# Relays.net
KiCad netlist of a schematic drawn in Altium Designer
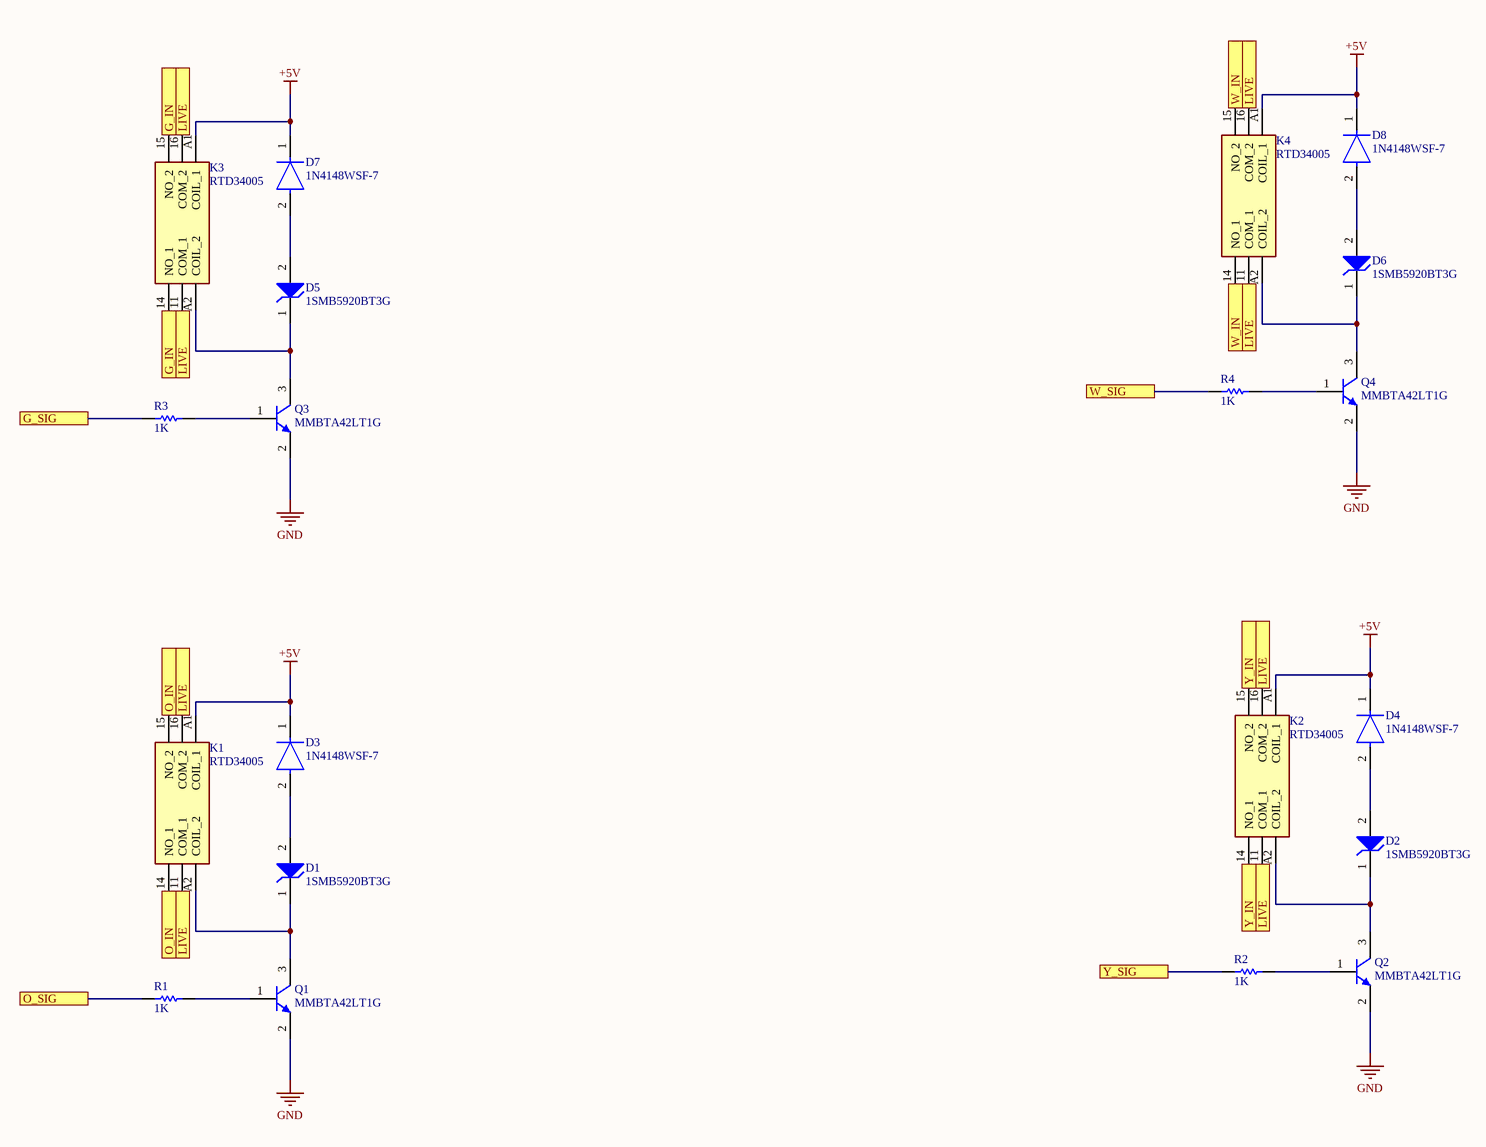
[diagram p0: Relays.SchDoc]

(export (version "E")
  (design (tool "Eeschema 10.0.6"))
  (components
    (comp (ref "D1")
      (value "1SMB5920BT3G")
      (footprint "ONSC-SMB-2-403A-03_H_V")
      (description "3 W Zener Voltage Regulator, 2-Pin SMB, Pb-Free, Tape and Reel")
      (fields (field (name "MANUFACTURER") "On Semiconductor"))
      (libsource (lib "Altium Content Vault") (part "ONSC-K1A2-2"))
    )
    (comp (ref "D2")
      (value "1SMB5920BT3G")
      (footprint "ONSC-SMB-2-403A-03_H_V")
      (description "3 W Zener Voltage Regulator, 2-Pin SMB, Pb-Free, Tape and Reel")
      (fields (field (name "MANUFACTURER") "On Semiconductor"))
      (libsource (lib "Altium Content Vault") (part "ONSC-K1A2-2"))
    )
    (comp (ref "D3")
      (value "1N4148WSF-7")
      (footprint "FP-SOD323F-MFG")
      (description "DIODE GEN PURP 100V 250MA SOD323")
      (fields
        (field (name "MANUFACTURER") "Diodes Inc.")
        (field (name "OCTOPART") "https://octopart.com/1n4148wsf-7-diodes+inc.-33798544")
      )
      (libsource (lib "Altium Content Vault") (part "d7152d700b627762746794eb795d46e"))
    )
    (comp (ref "D4")
      (value "1N4148WSF-7")
      (footprint "FP-SOD323F-MFG")
      (description "DIODE GEN PURP 100V 250MA SOD323")
      (fields
        (field (name "MANUFACTURER") "Diodes Inc.")
        (field (name "OCTOPART") "https://octopart.com/1n4148wsf-7-diodes+inc.-33798544")
      )
      (libsource (lib "Altium Content Vault") (part "d7152d700b627762746794eb795d46e"))
    )
    (comp (ref "D5")
      (value "1SMB5920BT3G")
      (footprint "ONSC-SMB-2-403A-03_H_V")
      (description "3 W Zener Voltage Regulator, 2-Pin SMB, Pb-Free, Tape and Reel")
      (fields (field (name "MANUFACTURER") "On Semiconductor"))
      (libsource (lib "Altium Content Vault") (part "ONSC-K1A2-2"))
    )
    (comp (ref "D6")
      (value "1SMB5920BT3G")
      (footprint "ONSC-SMB-2-403A-03_H_V")
      (description "3 W Zener Voltage Regulator, 2-Pin SMB, Pb-Free, Tape and Reel")
      (fields (field (name "MANUFACTURER") "On Semiconductor"))
      (libsource (lib "Altium Content Vault") (part "ONSC-K1A2-2"))
    )
    (comp (ref "D7")
      (value "1N4148WSF-7")
      (footprint "FP-SOD323F-MFG")
      (description "DIODE GEN PURP 100V 250MA SOD323")
      (fields
        (field (name "MANUFACTURER") "Diodes Inc.")
        (field (name "OCTOPART") "https://octopart.com/1n4148wsf-7-diodes+inc.-33798544")
      )
      (libsource (lib "Altium Content Vault") (part "d7152d700b627762746794eb795d46e"))
    )
    (comp (ref "D8")
      (value "1N4148WSF-7")
      (footprint "FP-SOD323F-MFG")
      (description "DIODE GEN PURP 100V 250MA SOD323")
      (fields
        (field (name "MANUFACTURER") "Diodes Inc.")
        (field (name "OCTOPART") "https://octopart.com/1n4148wsf-7-diodes+inc.-33798544")
      )
      (libsource (lib "Altium Content Vault") (part "d7152d700b627762746794eb795d46e"))
    )
    (comp (ref "K1")
      (value "RTD34005")
      (footprint "SamacSys:RTD34005")
      (description "Relay or Contactor")
      (fields (field (name "MOUSER PART NUMBER") "655-RTD34005"))
      (libsource (lib "*") (part "RTD34005"))
    )
    (comp (ref "K2")
      (value "RTD34005")
      (footprint "SamacSys:RTD34005")
      (description "Relay or Contactor")
      (fields (field (name "MOUSER PART NUMBER") "655-RTD34005"))
      (libsource (lib "*") (part "RTD34005"))
    )
    (comp (ref "K3")
      (value "RTD34005")
      (footprint "SamacSys:RTD34005")
      (description "Relay or Contactor")
      (fields (field (name "MOUSER PART NUMBER") "655-RTD34005"))
      (libsource (lib "*") (part "RTD34005"))
    )
    (comp (ref "K4")
      (value "RTD34005")
      (footprint "SamacSys:RTD34005")
      (description "Relay or Contactor")
      (fields (field (name "MOUSER PART NUMBER") "655-RTD34005"))
      (libsource (lib "*") (part "RTD34005"))
    )
    (comp (ref "Q1")
      (value "MMBTA42LT1G")
      (footprint "ONSC-SOT-23-3-318-08_V")
      (description "High Voltage Transistor, NPN Silicon, 3-Pin SOT-23, Pb-Free, Tape and Reel")
      (fields (field (name "MANUFACTURER") "On Semiconductor"))
      (libsource (lib "Altium Content Vault") (part "ONSC-NPN-B1E2C3-3"))
    )
    (comp (ref "Q2")
      (value "MMBTA42LT1G")
      (footprint "ONSC-SOT-23-3-318-08_V")
      (description "High Voltage Transistor, NPN Silicon, 3-Pin SOT-23, Pb-Free, Tape and Reel")
      (fields (field (name "MANUFACTURER") "On Semiconductor"))
      (libsource (lib "Altium Content Vault") (part "ONSC-NPN-B1E2C3-3"))
    )
    (comp (ref "Q3")
      (value "MMBTA42LT1G")
      (footprint "ONSC-SOT-23-3-318-08_V")
      (description "High Voltage Transistor, NPN Silicon, 3-Pin SOT-23, Pb-Free, Tape and Reel")
      (fields (field (name "MANUFACTURER") "On Semiconductor"))
      (libsource (lib "Altium Content Vault") (part "ONSC-NPN-B1E2C3-3"))
    )
    (comp (ref "Q4")
      (value "MMBTA42LT1G")
      (footprint "ONSC-SOT-23-3-318-08_V")
      (description "High Voltage Transistor, NPN Silicon, 3-Pin SOT-23, Pb-Free, Tape and Reel")
      (fields (field (name "MANUFACTURER") "On Semiconductor"))
      (libsource (lib "Altium Content Vault") (part "ONSC-NPN-B1E2C3-3"))
    )
    (comp (ref "R1")
      (value "1K")
      (footprint "RESC1608X55X30LL20T20")
      (fields (field (name "MANUFACTURER") "Panasonic") (field (name "PART NUMBER") "ERA3AEB102V"))
      (libsource (lib "Altium Content Vault") (part "RES"))
    )
    (comp (ref "R2")
      (value "1K")
      (footprint "RESC1608X55X30LL20T20")
      (fields (field (name "MANUFACTURER") "Panasonic") (field (name "PART NUMBER") "ERA3AEB102V"))
      (libsource (lib "Altium Content Vault") (part "RES"))
    )
    (comp (ref "R3")
      (value "1K")
      (footprint "RESC1608X55X30LL20T20")
      (fields (field (name "MANUFACTURER") "Panasonic") (field (name "PART NUMBER") "ERA3AEB102V"))
      (libsource (lib "Altium Content Vault") (part "RES"))
    )
    (comp (ref "R4")
      (value "1K")
      (footprint "RESC1608X55X30LL20T20")
      (fields (field (name "MANUFACTURER") "Panasonic") (field (name "PART NUMBER") "ERA3AEB102V"))
      (libsource (lib "Altium Content Vault") (part "RES"))
    )
  )
  (nets
    (net (code "1") (name "+5V") (class "Default")
      (node (ref "D3") (pin "1") (pinfunction "C_1") (pintype "passive"))
      (node (ref "D4") (pin "1") (pinfunction "C_1") (pintype "passive"))
      (node (ref "D7") (pin "1") (pinfunction "C_1") (pintype "passive"))
      (node (ref "D8") (pin "1") (pinfunction "C_1") (pintype "passive"))
      (node (ref "K1") (pin "A1") (pinfunction "COIL_1_A1") (pintype "passive"))
      (node (ref "K2") (pin "A1") (pinfunction "COIL_1_A1") (pintype "passive"))
      (node (ref "K3") (pin "A1") (pinfunction "COIL_1_A1") (pintype "passive"))
      (node (ref "K4") (pin "A1") (pinfunction "COIL_1_A1") (pintype "passive"))
    )
    (net (code "2") (name "/G_IN") (class "Default")
      (node (ref "K3") (pin "14") (pinfunction "NO_1_14") (pintype "passive"))
      (node (ref "K3") (pin "15") (pinfunction "NO_2_15") (pintype "passive"))
    )
    (net (code "3") (name "/G_SIG") (class "Default")
      (node (ref "R3") (pin "1") (pinfunction "1_1") (pintype "passive"))
    )
    (net (code "4") (name "/LIVE") (class "Default")
      (node (ref "K1") (pin "11") (pinfunction "COM_1_11") (pintype "passive"))
      (node (ref "K1") (pin "16") (pinfunction "COM_2_16") (pintype "passive"))
      (node (ref "K2") (pin "11") (pinfunction "COM_1_11") (pintype "passive"))
      (node (ref "K2") (pin "16") (pinfunction "COM_2_16") (pintype "passive"))
      (node (ref "K3") (pin "11") (pinfunction "COM_1_11") (pintype "passive"))
      (node (ref "K3") (pin "16") (pinfunction "COM_2_16") (pintype "passive"))
      (node (ref "K4") (pin "11") (pinfunction "COM_1_11") (pintype "passive"))
      (node (ref "K4") (pin "16") (pinfunction "COM_2_16") (pintype "passive"))
    )
    (net (code "5") (name "/O_IN") (class "Default")
      (node (ref "K1") (pin "14") (pinfunction "NO_1_14") (pintype "passive"))
      (node (ref "K1") (pin "15") (pinfunction "NO_2_15") (pintype "passive"))
    )
    (net (code "6") (name "/O_SIG") (class "Default")
      (node (ref "R1") (pin "1") (pinfunction "1_1") (pintype "passive"))
    )
    (net (code "7") (name "/W_IN") (class "Default")
      (node (ref "K4") (pin "14") (pinfunction "NO_1_14") (pintype "passive"))
      (node (ref "K4") (pin "15") (pinfunction "NO_2_15") (pintype "passive"))
    )
    (net (code "8") (name "/W_SIG") (class "Default")
      (node (ref "R4") (pin "1") (pinfunction "1_1") (pintype "passive"))
    )
    (net (code "9") (name "/Y_IN") (class "Default")
      (node (ref "K2") (pin "14") (pinfunction "NO_1_14") (pintype "passive"))
      (node (ref "K2") (pin "15") (pinfunction "NO_2_15") (pintype "passive"))
    )
    (net (code "10") (name "/Y_SIG") (class "Default")
      (node (ref "R2") (pin "1") (pinfunction "1_1") (pintype "passive"))
    )
    (net (code "11") (name "GND") (class "Default")
      (node (ref "Q1") (pin "2") (pinfunction "E_2") (pintype "passive"))
      (node (ref "Q2") (pin "2") (pinfunction "E_2") (pintype "passive"))
      (node (ref "Q3") (pin "2") (pinfunction "E_2") (pintype "passive"))
      (node (ref "Q4") (pin "2") (pinfunction "E_2") (pintype "passive"))
    )
    (net (code "12") (name "Net-(D1-A)") (class "Default")
      (node (ref "D1") (pin "2") (pinfunction "A_2") (pintype "passive"))
      (node (ref "D3") (pin "2") (pinfunction "A_2") (pintype "passive"))
    )
    (net (code "13") (name "Net-(D1-K)") (class "Default")
      (node (ref "D1") (pin "1") (pinfunction "K_1") (pintype "passive"))
      (node (ref "K1") (pin "A2") (pinfunction "COIL_2_A2") (pintype "passive"))
      (node (ref "Q1") (pin "3") (pinfunction "C_3") (pintype "passive"))
    )
    (net (code "14") (name "Net-(D2-A)") (class "Default")
      (node (ref "D2") (pin "2") (pinfunction "A_2") (pintype "passive"))
      (node (ref "D4") (pin "2") (pinfunction "A_2") (pintype "passive"))
    )
    (net (code "15") (name "Net-(D2-K)") (class "Default")
      (node (ref "D2") (pin "1") (pinfunction "K_1") (pintype "passive"))
      (node (ref "K2") (pin "A2") (pinfunction "COIL_2_A2") (pintype "passive"))
      (node (ref "Q2") (pin "3") (pinfunction "C_3") (pintype "passive"))
    )
    (net (code "16") (name "Net-(D5-A)") (class "Default")
      (node (ref "D5") (pin "2") (pinfunction "A_2") (pintype "passive"))
      (node (ref "D7") (pin "2") (pinfunction "A_2") (pintype "passive"))
    )
    (net (code "17") (name "Net-(D5-K)") (class "Default")
      (node (ref "D5") (pin "1") (pinfunction "K_1") (pintype "passive"))
      (node (ref "K3") (pin "A2") (pinfunction "COIL_2_A2") (pintype "passive"))
      (node (ref "Q3") (pin "3") (pinfunction "C_3") (pintype "passive"))
    )
    (net (code "18") (name "Net-(D6-A)") (class "Default")
      (node (ref "D6") (pin "2") (pinfunction "A_2") (pintype "passive"))
      (node (ref "D8") (pin "2") (pinfunction "A_2") (pintype "passive"))
    )
    (net (code "19") (name "Net-(D6-K)") (class "Default")
      (node (ref "D6") (pin "1") (pinfunction "K_1") (pintype "passive"))
      (node (ref "K4") (pin "A2") (pinfunction "COIL_2_A2") (pintype "passive"))
      (node (ref "Q4") (pin "3") (pinfunction "C_3") (pintype "passive"))
    )
    (net (code "20") (name "Net-(Q1-B)") (class "Default")
      (node (ref "Q1") (pin "1") (pinfunction "B_1") (pintype "passive"))
      (node (ref "R1") (pin "2") (pinfunction "2_2") (pintype "passive"))
    )
    (net (code "21") (name "Net-(Q2-B)") (class "Default")
      (node (ref "Q2") (pin "1") (pinfunction "B_1") (pintype "passive"))
      (node (ref "R2") (pin "2") (pinfunction "2_2") (pintype "passive"))
    )
    (net (code "22") (name "Net-(Q3-B)") (class "Default")
      (node (ref "Q3") (pin "1") (pinfunction "B_1") (pintype "passive"))
      (node (ref "R3") (pin "2") (pinfunction "2_2") (pintype "passive"))
    )
    (net (code "23") (name "Net-(Q4-B)") (class "Default")
      (node (ref "Q4") (pin "1") (pinfunction "B_1") (pintype "passive"))
      (node (ref "R4") (pin "2") (pinfunction "2_2") (pintype "passive"))
    )
  )
)
